# FAT42.net
KiCad netlist of a schematic drawn in Altium Designer
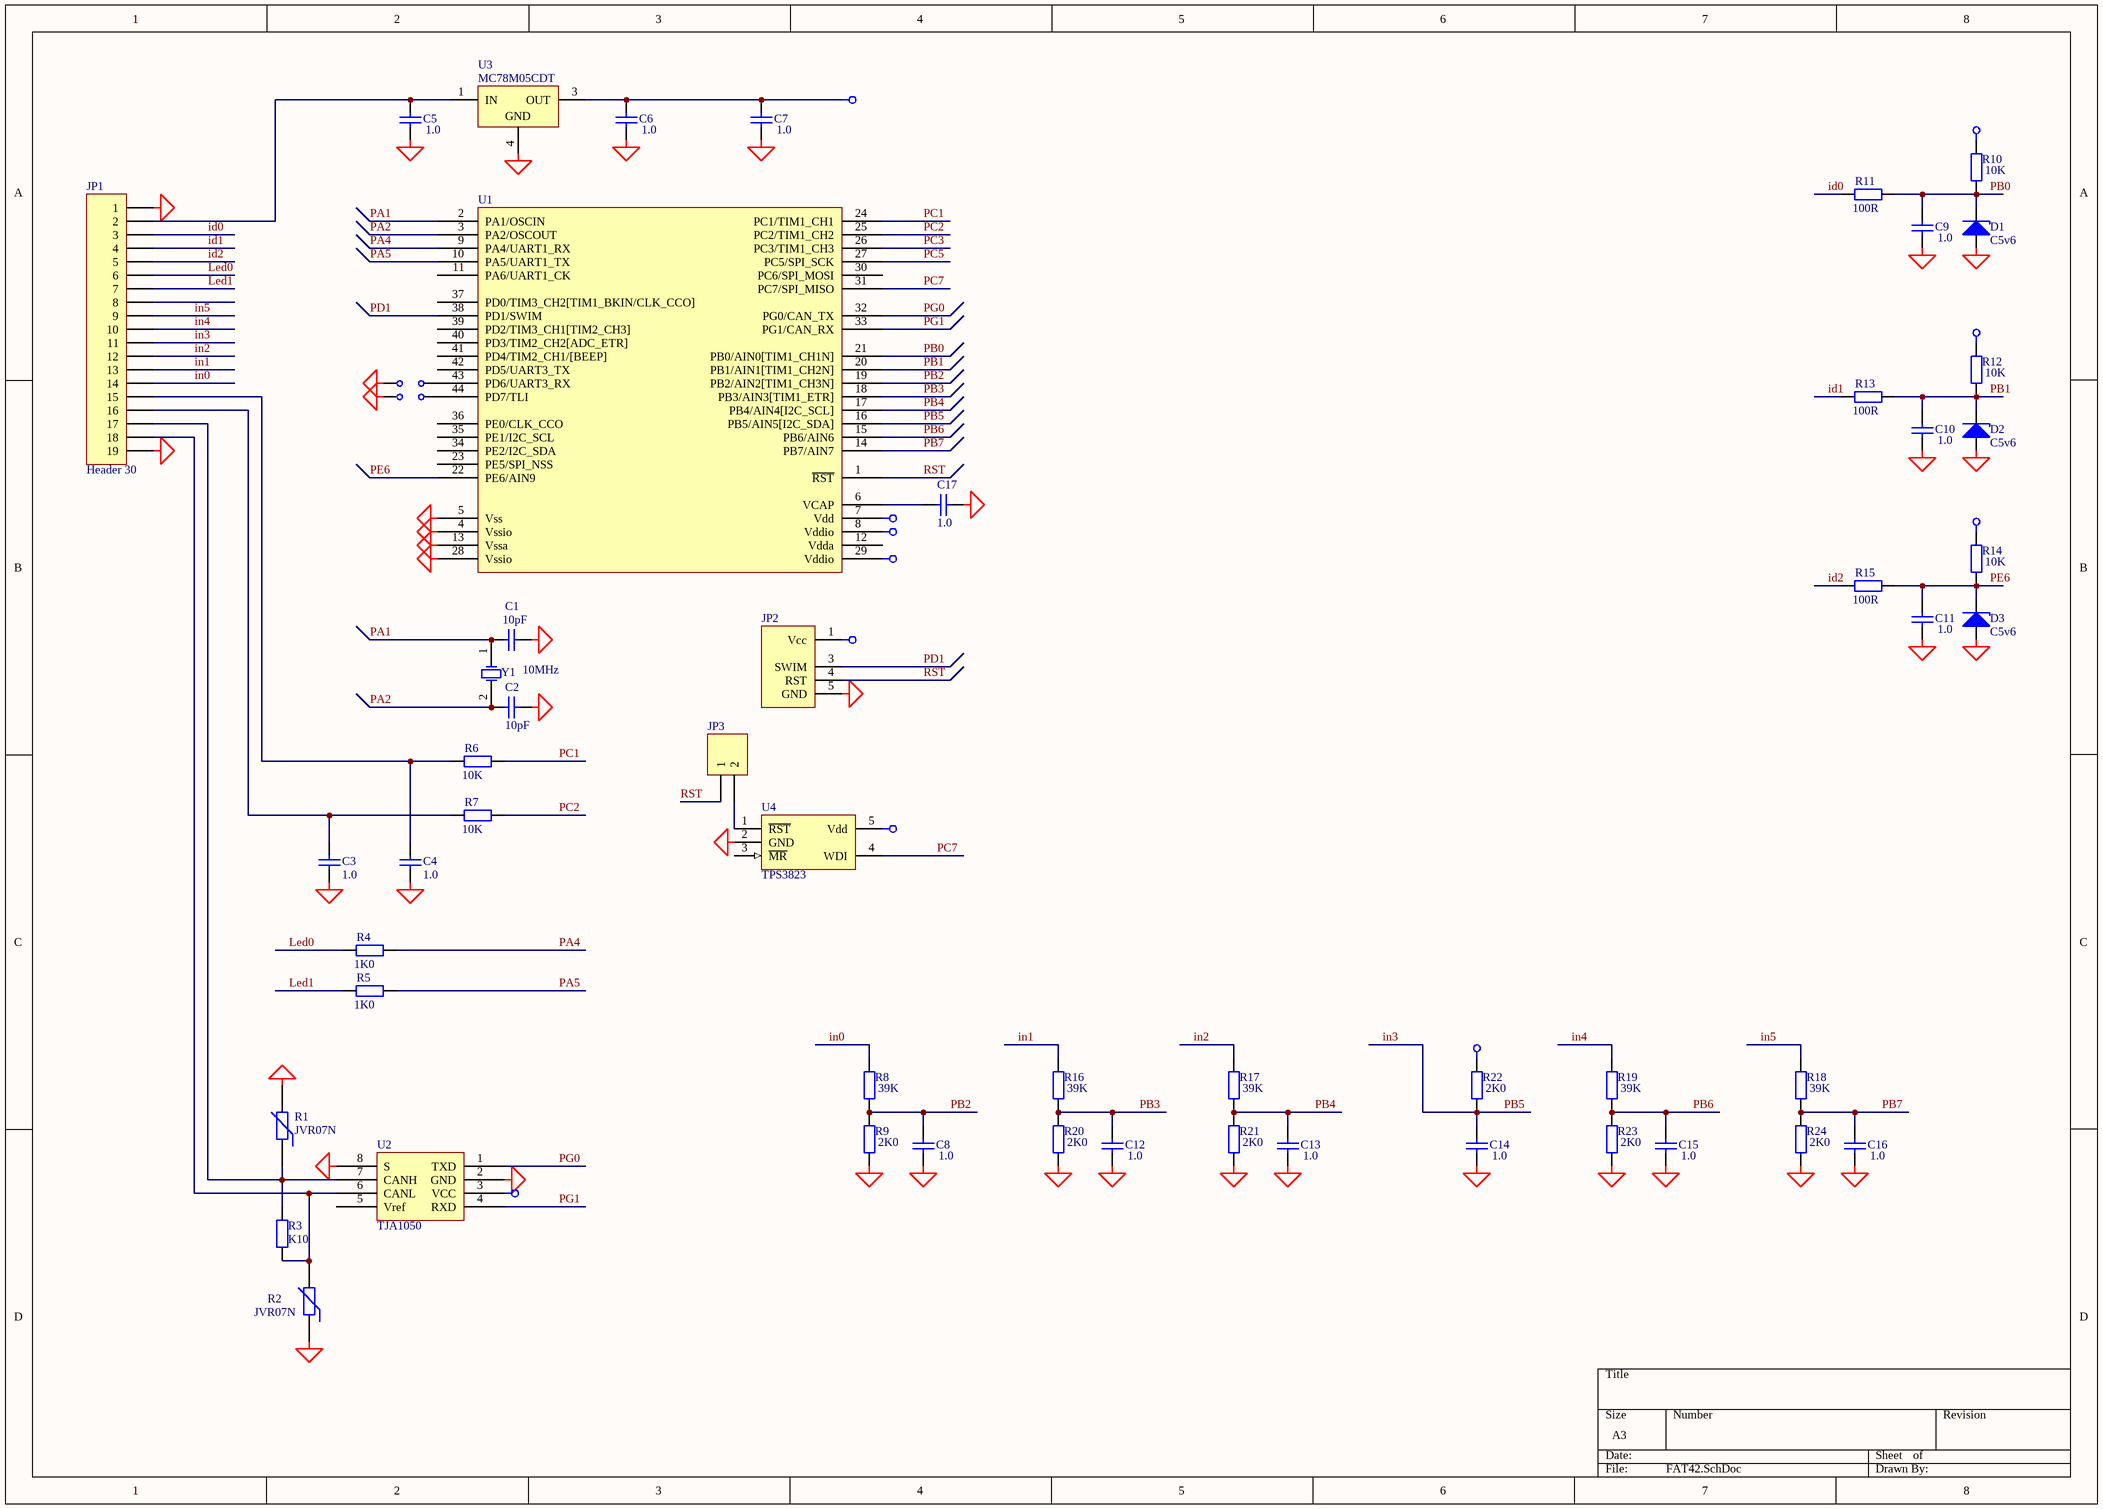
[diagram p0: FAT42.SchDoc]

(export (version "E")
  (design (tool "Eeschema 10.0.6"))
  (components
    (comp (ref "C1")
      (value "10pF")
      (footprint "_1206")
      (description "Capacitor (Semiconductor SIM Model)")
      (fields (field (name "MANUFACTURER") "Generic Components") (field (name "PUBLISHER") "Altium Limited"))
      (libsource (lib "Miscellaneous Devices") (part "Cap Semi"))
    )
    (comp (ref "C2")
      (value "10pF")
      (footprint "_1206")
      (description "Capacitor (Semiconductor SIM Model)")
      (fields (field (name "MANUFACTURER") "Generic Components") (field (name "PUBLISHER") "Altium Limited"))
      (libsource (lib "Miscellaneous Devices") (part "Cap Semi"))
    )
    (comp (ref "C3")
      (value "1.0")
      (footprint "_1206")
      (description "Capacitor (Semiconductor SIM Model)")
      (fields (field (name "MANUFACTURER") "Generic Components") (field (name "PUBLISHER") "Altium Limited"))
      (libsource (lib "Miscellaneous Devices") (part "Cap Semi"))
    )
    (comp (ref "C4")
      (value "1.0")
      (footprint "_1206")
      (description "Capacitor (Semiconductor SIM Model)")
      (fields (field (name "MANUFACTURER") "Generic Components") (field (name "PUBLISHER") "Altium Limited"))
      (libsource (lib "Miscellaneous Devices") (part "Cap Semi"))
    )
    (comp (ref "C5")
      (value "1.0")
      (footprint "_1206")
      (description "Capacitor (Semiconductor SIM Model)")
      (fields (field (name "MANUFACTURER") "Generic Components") (field (name "PUBLISHER") "Altium Limited"))
      (libsource (lib "Miscellaneous Devices") (part "Cap Semi"))
    )
    (comp (ref "C6")
      (value "1.0")
      (footprint "_1206")
      (description "Capacitor (Semiconductor SIM Model)")
      (fields (field (name "MANUFACTURER") "Generic Components") (field (name "PUBLISHER") "Altium Limited"))
      (libsource (lib "Miscellaneous Devices") (part "Cap Semi"))
    )
    (comp (ref "C7")
      (value "1.0")
      (footprint "_1206")
      (description "Capacitor (Semiconductor SIM Model)")
      (fields (field (name "MANUFACTURER") "Generic Components") (field (name "PUBLISHER") "Altium Limited"))
      (libsource (lib "Miscellaneous Devices") (part "Cap Semi"))
    )
    (comp (ref "C8")
      (value "1.0")
      (footprint "_1206")
      (description "Capacitor (Semiconductor SIM Model)")
      (fields (field (name "MANUFACTURER") "Generic Components") (field (name "PUBLISHER") "Altium Limited"))
      (libsource (lib "Miscellaneous Devices") (part "Cap Semi"))
    )
    (comp (ref "C9")
      (value "1.0")
      (footprint "_1206")
      (description "Capacitor (Semiconductor SIM Model)")
      (fields (field (name "MANUFACTURER") "Generic Components") (field (name "PUBLISHER") "Altium Limited"))
      (libsource (lib "Miscellaneous Devices") (part "Cap Semi"))
    )
    (comp (ref "C10")
      (value "1.0")
      (footprint "_1206")
      (description "Capacitor (Semiconductor SIM Model)")
      (fields (field (name "MANUFACTURER") "Generic Components") (field (name "PUBLISHER") "Altium Limited"))
      (libsource (lib "Miscellaneous Devices") (part "Cap Semi"))
    )
    (comp (ref "C11")
      (value "1.0")
      (footprint "_1206")
      (description "Capacitor (Semiconductor SIM Model)")
      (fields (field (name "MANUFACTURER") "Generic Components") (field (name "PUBLISHER") "Altium Limited"))
      (libsource (lib "Miscellaneous Devices") (part "Cap Semi"))
    )
    (comp (ref "C12")
      (value "1.0")
      (footprint "_1206")
      (description "Capacitor (Semiconductor SIM Model)")
      (fields (field (name "MANUFACTURER") "Generic Components") (field (name "PUBLISHER") "Altium Limited"))
      (libsource (lib "Miscellaneous Devices") (part "Cap Semi"))
    )
    (comp (ref "C13")
      (value "1.0")
      (footprint "_1206")
      (description "Capacitor (Semiconductor SIM Model)")
      (fields (field (name "MANUFACTURER") "Generic Components") (field (name "PUBLISHER") "Altium Limited"))
      (libsource (lib "Miscellaneous Devices") (part "Cap Semi"))
    )
    (comp (ref "C14")
      (value "1.0")
      (footprint "_1206")
      (description "Capacitor (Semiconductor SIM Model)")
      (fields (field (name "MANUFACTURER") "Generic Components") (field (name "PUBLISHER") "Altium Limited"))
      (libsource (lib "Miscellaneous Devices") (part "Cap Semi"))
    )
    (comp (ref "C15")
      (value "1.0")
      (footprint "_1206")
      (description "Capacitor (Semiconductor SIM Model)")
      (fields (field (name "MANUFACTURER") "Generic Components") (field (name "PUBLISHER") "Altium Limited"))
      (libsource (lib "Miscellaneous Devices") (part "Cap Semi"))
    )
    (comp (ref "C16")
      (value "1.0")
      (footprint "_1206")
      (description "Capacitor (Semiconductor SIM Model)")
      (fields (field (name "MANUFACTURER") "Generic Components") (field (name "PUBLISHER") "Altium Limited"))
      (libsource (lib "Miscellaneous Devices") (part "Cap Semi"))
    )
    (comp (ref "C17")
      (value "1.0")
      (footprint "_1206")
      (description "Capacitor (Semiconductor SIM Model)")
      (fields (field (name "MANUFACTURER") "Generic Components") (field (name "PUBLISHER") "Altium Limited"))
      (libsource (lib "Miscellaneous Devices") (part "Cap Semi"))
    )
    (comp (ref "D1")
      (value "C5v6")
      (footprint "_1206d")
      (description "Default Diode")
      (fields (field (name "MANUFACTURER") "Generic Components") (field (name "PUBLISHER") "Altium Limited"))
      (libsource (lib "PAL") (part "Zener"))
    )
    (comp (ref "D2")
      (value "C5v6")
      (footprint "_1206d")
      (description "Default Diode")
      (fields (field (name "MANUFACTURER") "Generic Components") (field (name "PUBLISHER") "Altium Limited"))
      (libsource (lib "PAL") (part "Zener"))
    )
    (comp (ref "D3")
      (value "C5v6")
      (footprint "_1206d")
      (description "Default Diode")
      (fields (field (name "MANUFACTURER") "Generic Components") (field (name "PUBLISHER") "Altium Limited"))
      (libsource (lib "PAL") (part "Zener"))
    )
    (comp (ref "J1")
      (value "~")
      (footprint "jmp")
      (description "Switch")
      (fields (field (name "MANUFACTURER") "Generic Components") (field (name "PUBLISHER") "Altium Limited"))
      (libsource (lib "PAL") (part "JMP"))
    )
    (comp (ref "J2")
      (value "~")
      (footprint "jmp")
      (description "Switch")
      (fields (field (name "MANUFACTURER") "Generic Components") (field (name "PUBLISHER") "Altium Limited"))
      (libsource (lib "PAL") (part "JMP"))
    )
    (comp (ref "JP1")
      (value "Header 30")
      (footprint "HDR1X19")
      (description "Header, 19-Pin")
      (fields (field (name "MANUFACTURER") "Generic Components") (field (name "PUBLISHER") "Altium Limited"))
      (libsource (lib "Miscellaneous Connectors") (part "Header 19"))
    )
    (comp (ref "JP2") (value "~") (footprint "HDR1X5_uart") (libsource (lib "PAL") (part "SWIM_CONN")))
    (comp (ref "JP3")
      (value "PLS2")
      (footprint "HDR1X2")
      (description "Header, 2-Pin")
      (fields (field (name "MANUFACTURER") "Generic Components") (field (name "PUBLISHER") "Altium Limited"))
      (libsource (lib "Miscellaneous Connectors") (part "Header 2"))
    )
    (comp (ref "R1")
      (value "JVR07N")
      (footprint "JVR07N")
      (description "Varistor (Voltage-Sensitive Resistor)")
      (fields (field (name "MANUFACTURER") "Generic Components") (field (name "PUBLISHER") "Altium Limited"))
      (libsource (lib "Miscellaneous Devices") (part "Res Varistor"))
    )
    (comp (ref "R2")
      (value "JVR07N")
      (footprint "JVR07N")
      (description "Varistor (Voltage-Sensitive Resistor)")
      (fields (field (name "MANUFACTURER") "Generic Components") (field (name "PUBLISHER") "Altium Limited"))
      (libsource (lib "Miscellaneous Devices") (part "Res Varistor"))
    )
    (comp (ref "R3")
      (value "K10")
      (footprint "_1206")
      (description "Resistor")
      (fields (field (name "MANUFACTURER") "Generic Components") (field (name "PUBLISHER") "Altium Limited"))
      (libsource (lib "") (part "Res2_4"))
    )
    (comp (ref "R4")
      (value "1K0")
      (footprint "_1206")
      (description "Resistor")
      (fields (field (name "MANUFACTURER") "Generic Components") (field (name "PUBLISHER") "Altium Limited"))
      (libsource (lib "") (part "Res2_3"))
    )
    (comp (ref "R5")
      (value "1K0")
      (footprint "_1206")
      (description "Resistor")
      (fields (field (name "MANUFACTURER") "Generic Components") (field (name "PUBLISHER") "Altium Limited"))
      (libsource (lib "") (part "Res2_3"))
    )
    (comp (ref "R6")
      (value "10K")
      (footprint "_1206")
      (description "Resistor")
      (fields (field (name "MANUFACTURER") "Generic Components") (field (name "PUBLISHER") "Altium Limited"))
      (libsource (lib "") (part "Res2_1"))
    )
    (comp (ref "R7")
      (value "10K")
      (footprint "_1206")
      (description "Resistor")
      (fields (field (name "MANUFACTURER") "Generic Components") (field (name "PUBLISHER") "Altium Limited"))
      (libsource (lib "") (part "Res2_1"))
    )
    (comp (ref "R8")
      (value "39K")
      (footprint "_1206")
      (description "Resistor")
      (fields (field (name "MANUFACTURER") "Generic Components") (field (name "PUBLISHER") "Altium Limited"))
      (libsource (lib "Miscellaneous Devices") (part "Res2"))
    )
    (comp (ref "R9")
      (value "2K0")
      (footprint "_1206")
      (description "Resistor")
      (fields (field (name "MANUFACTURER") "Generic Components") (field (name "PUBLISHER") "Altium Limited"))
      (libsource (lib "Miscellaneous Devices") (part "Res2"))
    )
    (comp (ref "R10")
      (value "10K")
      (footprint "_1206")
      (description "Resistor")
      (fields (field (name "MANUFACTURER") "Generic Components") (field (name "PUBLISHER") "Altium Limited"))
      (libsource (lib "") (part "Res2_2"))
    )
    (comp (ref "R11")
      (value "100R")
      (footprint "_1206")
      (description "Resistor")
      (fields (field (name "MANUFACTURER") "Generic Components") (field (name "PUBLISHER") "Altium Limited"))
      (libsource (lib "") (part "Res2_1"))
    )
    (comp (ref "R12")
      (value "10K")
      (footprint "_1206")
      (description "Resistor")
      (fields (field (name "MANUFACTURER") "Generic Components") (field (name "PUBLISHER") "Altium Limited"))
      (libsource (lib "") (part "Res2_2"))
    )
    (comp (ref "R13")
      (value "100R")
      (footprint "_1206")
      (description "Resistor")
      (fields (field (name "MANUFACTURER") "Generic Components") (field (name "PUBLISHER") "Altium Limited"))
      (libsource (lib "") (part "Res2_1"))
    )
    (comp (ref "R14")
      (value "10K")
      (footprint "_1206")
      (description "Resistor")
      (fields (field (name "MANUFACTURER") "Generic Components") (field (name "PUBLISHER") "Altium Limited"))
      (libsource (lib "") (part "Res2_2"))
    )
    (comp (ref "R15")
      (value "100R")
      (footprint "_1206")
      (description "Resistor")
      (fields (field (name "MANUFACTURER") "Generic Components") (field (name "PUBLISHER") "Altium Limited"))
      (libsource (lib "") (part "Res2_1"))
    )
    (comp (ref "R16")
      (value "39K")
      (footprint "_1206")
      (description "Resistor")
      (fields (field (name "MANUFACTURER") "Generic Components") (field (name "PUBLISHER") "Altium Limited"))
      (libsource (lib "Miscellaneous Devices") (part "Res2"))
    )
    (comp (ref "R17")
      (value "39K")
      (footprint "_1206")
      (description "Resistor")
      (fields (field (name "MANUFACTURER") "Generic Components") (field (name "PUBLISHER") "Altium Limited"))
      (libsource (lib "Miscellaneous Devices") (part "Res2"))
    )
    (comp (ref "R18")
      (value "39K")
      (footprint "_1206")
      (description "Resistor")
      (fields (field (name "MANUFACTURER") "Generic Components") (field (name "PUBLISHER") "Altium Limited"))
      (libsource (lib "Miscellaneous Devices") (part "Res2"))
    )
    (comp (ref "R19")
      (value "39K")
      (footprint "_1206")
      (description "Resistor")
      (fields (field (name "MANUFACTURER") "Generic Components") (field (name "PUBLISHER") "Altium Limited"))
      (libsource (lib "Miscellaneous Devices") (part "Res2"))
    )
    (comp (ref "R20")
      (value "2K0")
      (footprint "_1206")
      (description "Resistor")
      (fields (field (name "MANUFACTURER") "Generic Components") (field (name "PUBLISHER") "Altium Limited"))
      (libsource (lib "Miscellaneous Devices") (part "Res2"))
    )
    (comp (ref "R21")
      (value "2K0")
      (footprint "_1206")
      (description "Resistor")
      (fields (field (name "MANUFACTURER") "Generic Components") (field (name "PUBLISHER") "Altium Limited"))
      (libsource (lib "Miscellaneous Devices") (part "Res2"))
    )
    (comp (ref "R22")
      (value "2K0")
      (footprint "_1206")
      (description "Resistor")
      (fields (field (name "MANUFACTURER") "Generic Components") (field (name "PUBLISHER") "Altium Limited"))
      (libsource (lib "Miscellaneous Devices") (part "Res2"))
    )
    (comp (ref "R23")
      (value "2K0")
      (footprint "_1206")
      (description "Resistor")
      (fields (field (name "MANUFACTURER") "Generic Components") (field (name "PUBLISHER") "Altium Limited"))
      (libsource (lib "Miscellaneous Devices") (part "Res2"))
    )
    (comp (ref "R24")
      (value "2K0")
      (footprint "_1206")
      (description "Resistor")
      (fields (field (name "MANUFACTURER") "Generic Components") (field (name "PUBLISHER") "Altium Limited"))
      (libsource (lib "Miscellaneous Devices") (part "Res2"))
    )
    (comp (ref "U1") (value "~") (footprint "QFP10X10-G44/G10N") (libsource (lib "PAL") (part "STM8S208S6")))
    (comp (ref "U2") (value "TJA1050") (footprint "SO-G8/D5") (libsource (lib "PAL") (part "TJA1050")))
    (comp (ref "U3")
      (value "MC78M05CDT")
      (footprint "SIP-G3/Z11.05")
      (description "Three-Terminal Medium Current Positive Voltage Regulator")
      (fields (field (name "MANUFACTURER") "ON Semiconductor") (field (name "PUBLISHER") "Altium Limited"))
      (libsource (lib "ON Semi Power Mgt Voltage Regulator") (part "MC78M05CDT"))
    )
    (comp (ref "U4")
      (value "TPS3823")
      (footprint "SO-G5/P.95")
      (description "Reset IC")
      (fields
        (field (name "MANUFACTURER") "National Semiconductor")
        (field (name "PUBLISHER") "Altium Limited")
      )
      (libsource (lib "PAL") (part "TPS3823"))
    )
    (comp (ref "Y1")
      (value "10MHz")
      (footprint "QWARZ1")
      (description "Crystal Oscillator")
      (fields (field (name "MANUFACTURER") "Generic Components") (field (name "PUBLISHER") "Altium Limited"))
      (libsource (lib "Miscellaneous Devices") (part "XTAL"))
    )
  )
  (nets
    (net (code "1") (name "+5v") (class "Default")
      (node (ref "C6") (pin "2") (pinfunction "2_2") (pintype "passive"))
      (node (ref "C7") (pin "2") (pinfunction "2_2") (pintype "passive"))
      (node (ref "JP2") (pin "1") (pinfunction "Vcc_1") (pintype "passive"))
      (node (ref "R10") (pin "1") (pinfunction "1_1") (pintype "passive"))
      (node (ref "R12") (pin "1") (pinfunction "1_1") (pintype "passive"))
      (node (ref "R14") (pin "1") (pinfunction "1_1") (pintype "passive"))
      (node (ref "R22") (pin "2") (pinfunction "2_2") (pintype "passive"))
      (node (ref "U1") (pin "29") (pinfunction "Vddio_29") (pintype "passive"))
      (node (ref "U1") (pin "7") (pinfunction "Vdd_7") (pintype "passive"))
      (node (ref "U1") (pin "8") (pinfunction "Vddio_8") (pintype "passive"))
      (node (ref "U2") (pin "3") (pinfunction "VCC_3") (pintype "passive"))
      (node (ref "U3") (pin "3") (pinfunction "OUT_3") (pintype "power_in"))
      (node (ref "U4") (pin "5") (pinfunction "Vdd_5") (pintype "power_in"))
    )
    (net (code "2") (name "/Led0") (class "Default")
      (node (ref "JP1") (pin "6") (pinfunction "6_6") (pintype "passive"))
      (node (ref "R4") (pin "1") (pinfunction "1_1") (pintype "passive"))
    )
    (net (code "3") (name "/Led1") (class "Default")
      (node (ref "JP1") (pin "7") (pinfunction "7_7") (pintype "passive"))
      (node (ref "R5") (pin "1") (pinfunction "1_1") (pintype "passive"))
    )
    (net (code "4") (name "/PA1") (class "Default")
      (node (ref "C1") (pin "2") (pinfunction "2_2") (pintype "passive"))
      (node (ref "U1") (pin "2") (pinfunction "PA1/OSCIN_2") (pintype "passive"))
      (node (ref "Y1") (pin "1") (pinfunction "OSC1_1") (pintype "passive"))
    )
    (net (code "5") (name "/PA2") (class "Default")
      (node (ref "C2") (pin "2") (pinfunction "2_2") (pintype "passive"))
      (node (ref "U1") (pin "3") (pinfunction "PA2/OSCOUT_3") (pintype "passive"))
      (node (ref "Y1") (pin "2") (pinfunction "OSC2_2") (pintype "passive"))
    )
    (net (code "6") (name "/PA4") (class "Default")
      (node (ref "R4") (pin "2") (pinfunction "2_2") (pintype "passive"))
      (node (ref "U1") (pin "9") (pinfunction "PA4/UART1_RX_9") (pintype "passive"))
    )
    (net (code "7") (name "/PA5") (class "Default")
      (node (ref "R5") (pin "2") (pinfunction "2_2") (pintype "passive"))
      (node (ref "U1") (pin "10") (pinfunction "PA5/UART1_TX_10") (pintype "passive"))
    )
    (net (code "8") (name "/PB0") (class "Default")
      (node (ref "C9") (pin "2") (pinfunction "2_2") (pintype "passive"))
      (node (ref "D1") (pin "2") (pinfunction "K_2") (pintype "passive"))
      (node (ref "R10") (pin "2") (pinfunction "2_2") (pintype "passive"))
      (node (ref "R11") (pin "1") (pinfunction "1_1") (pintype "passive"))
      (node (ref "U1") (pin "21") (pinfunction "PB0/AIN0[TIM1_CH1N]_21") (pintype "passive"))
    )
    (net (code "9") (name "/PB1") (class "Default")
      (node (ref "C10") (pin "2") (pinfunction "2_2") (pintype "passive"))
      (node (ref "D2") (pin "2") (pinfunction "K_2") (pintype "passive"))
      (node (ref "R12") (pin "2") (pinfunction "2_2") (pintype "passive"))
      (node (ref "R13") (pin "1") (pinfunction "1_1") (pintype "passive"))
      (node (ref "U1") (pin "20") (pinfunction "PB1/AIN1[TIM1_CH2N]_20") (pintype "passive"))
    )
    (net (code "10") (name "/PB2") (class "Default")
      (node (ref "C8") (pin "2") (pinfunction "2_2") (pintype "passive"))
      (node (ref "R8") (pin "1") (pinfunction "1_1") (pintype "passive"))
      (node (ref "R9") (pin "2") (pinfunction "2_2") (pintype "passive"))
      (node (ref "U1") (pin "19") (pinfunction "PB2/AIN2[TIM1_CH3N]_19") (pintype "passive"))
    )
    (net (code "11") (name "/PB3") (class "Default")
      (node (ref "C12") (pin "2") (pinfunction "2_2") (pintype "passive"))
      (node (ref "R16") (pin "1") (pinfunction "1_1") (pintype "passive"))
      (node (ref "R20") (pin "2") (pinfunction "2_2") (pintype "passive"))
      (node (ref "U1") (pin "18") (pinfunction "PB3/AIN3[TIM1_ETR]_18") (pintype "passive"))
    )
    (net (code "12") (name "/PB4") (class "Default")
      (node (ref "C13") (pin "2") (pinfunction "2_2") (pintype "passive"))
      (node (ref "R17") (pin "1") (pinfunction "1_1") (pintype "passive"))
      (node (ref "R21") (pin "2") (pinfunction "2_2") (pintype "passive"))
      (node (ref "U1") (pin "17") (pinfunction "PB4/AIN4[I2C_SCL]_17") (pintype "passive"))
    )
    (net (code "13") (name "/PB5") (class "Default")
      (node (ref "C14") (pin "2") (pinfunction "2_2") (pintype "passive"))
      (node (ref "JP1") (pin "11") (pinfunction "11_11") (pintype "passive"))
      (node (ref "R22") (pin "1") (pinfunction "1_1") (pintype "passive"))
      (node (ref "U1") (pin "16") (pinfunction "PB5/AIN5[I2C_SDA]_16") (pintype "passive"))
    )
    (net (code "14") (name "/PB6") (class "Default")
      (node (ref "C15") (pin "2") (pinfunction "2_2") (pintype "passive"))
      (node (ref "R19") (pin "1") (pinfunction "1_1") (pintype "passive"))
      (node (ref "R23") (pin "2") (pinfunction "2_2") (pintype "passive"))
      (node (ref "U1") (pin "15") (pinfunction "PB6/AIN6_15") (pintype "passive"))
    )
    (net (code "15") (name "/PB7") (class "Default")
      (node (ref "C16") (pin "2") (pinfunction "2_2") (pintype "passive"))
      (node (ref "R18") (pin "1") (pinfunction "1_1") (pintype "passive"))
      (node (ref "R24") (pin "2") (pinfunction "2_2") (pintype "passive"))
      (node (ref "U1") (pin "14") (pinfunction "PB7/AIN7_14") (pintype "passive"))
    )
    (net (code "16") (name "/PC1") (class "Default")
      (node (ref "R6") (pin "1") (pinfunction "1_1") (pintype "passive"))
      (node (ref "U1") (pin "24") (pinfunction "PC1/TIM1_CH1_24") (pintype "passive"))
    )
    (net (code "17") (name "/PC2") (class "Default")
      (node (ref "R7") (pin "1") (pinfunction "1_1") (pintype "passive"))
      (node (ref "U1") (pin "25") (pinfunction "PC2/TIM1_CH2_25") (pintype "passive"))
    )
    (net (code "18") (name "/PC3") (class "Default")
      (node (ref "U1") (pin "26") (pinfunction "PC3/TIM1_CH3_26") (pintype "passive"))
    )
    (net (code "19") (name "/PC5") (class "Default")
      (node (ref "U1") (pin "27") (pinfunction "PC5/SPI_SCK_27") (pintype "passive"))
    )
    (net (code "20") (name "/PC7") (class "Default")
      (node (ref "U1") (pin "31") (pinfunction "PC7/SPI_MISO_31") (pintype "passive"))
      (node (ref "U4") (pin "4") (pinfunction "WDI_4") (pintype "passive"))
    )
    (net (code "21") (name "/PD1") (class "Default")
      (node (ref "JP2") (pin "3") (pinfunction "SWIM_3") (pintype "passive"))
      (node (ref "U1") (pin "38") (pinfunction "PD1/SWIM_38") (pintype "passive"))
    )
    (net (code "22") (name "/PE6") (class "Default")
      (node (ref "C11") (pin "2") (pinfunction "2_2") (pintype "passive"))
      (node (ref "D3") (pin "2") (pinfunction "K_2") (pintype "passive"))
      (node (ref "R14") (pin "2") (pinfunction "2_2") (pintype "passive"))
      (node (ref "R15") (pin "1") (pinfunction "1_1") (pintype "passive"))
      (node (ref "U1") (pin "22") (pinfunction "PE6/AIN9_22") (pintype "passive"))
    )
    (net (code "23") (name "/PG0") (class "Default")
      (node (ref "U1") (pin "32") (pinfunction "PG0/CAN_TX_32") (pintype "passive"))
      (node (ref "U2") (pin "1") (pinfunction "TXD_1") (pintype "passive"))
    )
    (net (code "24") (name "/PG1") (class "Default")
      (node (ref "U1") (pin "33") (pinfunction "PG1/CAN_RX_33") (pintype "passive"))
      (node (ref "U2") (pin "4") (pinfunction "RXD_4") (pintype "passive"))
    )
    (net (code "25") (name "/RST") (class "Default")
      (node (ref "JP2") (pin "4") (pinfunction "RST_4") (pintype "passive"))
      (node (ref "JP3") (pin "1") (pinfunction "1_1") (pintype "passive"))
      (node (ref "U1") (pin "1") (pinfunction "~{RST}_1") (pintype "passive"))
    )
    (net (code "26") (name "/id0") (class "Default")
      (node (ref "JP1") (pin "3") (pinfunction "3_3") (pintype "passive"))
      (node (ref "R11") (pin "2") (pinfunction "2_2") (pintype "passive"))
    )
    (net (code "27") (name "/id1") (class "Default")
      (node (ref "JP1") (pin "4") (pinfunction "4_4") (pintype "passive"))
      (node (ref "R13") (pin "2") (pinfunction "2_2") (pintype "passive"))
    )
    (net (code "28") (name "/id2") (class "Default")
      (node (ref "JP1") (pin "5") (pinfunction "5_5") (pintype "passive"))
      (node (ref "R15") (pin "2") (pinfunction "2_2") (pintype "passive"))
    )
    (net (code "29") (name "/in0") (class "Default")
      (node (ref "JP1") (pin "14") (pinfunction "14_14") (pintype "passive"))
      (node (ref "R8") (pin "2") (pinfunction "2_2") (pintype "passive"))
    )
    (net (code "30") (name "/in1") (class "Default")
      (node (ref "JP1") (pin "13") (pinfunction "13_13") (pintype "passive"))
      (node (ref "R16") (pin "2") (pinfunction "2_2") (pintype "passive"))
    )
    (net (code "31") (name "/in2") (class "Default")
      (node (ref "JP1") (pin "12") (pinfunction "12_12") (pintype "passive"))
      (node (ref "R17") (pin "2") (pinfunction "2_2") (pintype "passive"))
    )
    (net (code "32") (name "/in4") (class "Default")
      (node (ref "JP1") (pin "10") (pinfunction "10_10") (pintype "passive"))
      (node (ref "R19") (pin "2") (pinfunction "2_2") (pintype "passive"))
    )
    (net (code "33") (name "/in5") (class "Default")
      (node (ref "JP1") (pin "9") (pinfunction "9_9") (pintype "passive"))
      (node (ref "R18") (pin "2") (pinfunction "2_2") (pintype "passive"))
    )
    (net (code "34") (name "GND") (class "Default")
      (node (ref "C1") (pin "1") (pinfunction "1_1") (pintype "passive"))
      (node (ref "C10") (pin "1") (pinfunction "1_1") (pintype "passive"))
      (node (ref "C11") (pin "1") (pinfunction "1_1") (pintype "passive"))
      (node (ref "C12") (pin "1") (pinfunction "1_1") (pintype "passive"))
      (node (ref "C13") (pin "1") (pinfunction "1_1") (pintype "passive"))
      (node (ref "C14") (pin "1") (pinfunction "1_1") (pintype "passive"))
      (node (ref "C15") (pin "1") (pinfunction "1_1") (pintype "passive"))
      (node (ref "C16") (pin "1") (pinfunction "1_1") (pintype "passive"))
      (node (ref "C17") (pin "1") (pinfunction "1_1") (pintype "passive"))
      (node (ref "C2") (pin "1") (pinfunction "1_1") (pintype "passive"))
      (node (ref "C3") (pin "1") (pinfunction "1_1") (pintype "passive"))
      (node (ref "C4") (pin "1") (pinfunction "1_1") (pintype "passive"))
      (node (ref "C5") (pin "1") (pinfunction "1_1") (pintype "passive"))
      (node (ref "C6") (pin "1") (pinfunction "1_1") (pintype "passive"))
      (node (ref "C7") (pin "1") (pinfunction "1_1") (pintype "passive"))
      (node (ref "C8") (pin "1") (pinfunction "1_1") (pintype "passive"))
      (node (ref "C9") (pin "1") (pinfunction "1_1") (pintype "passive"))
      (node (ref "D1") (pin "1") (pinfunction "A_1") (pintype "passive"))
      (node (ref "D2") (pin "1") (pinfunction "A_1") (pintype "passive"))
      (node (ref "D3") (pin "1") (pinfunction "A_1") (pintype "passive"))
      (node (ref "J1") (pin "1") (pinfunction "1_1") (pintype "passive"))
      (node (ref "J2") (pin "1") (pinfunction "1_1") (pintype "passive"))
      (node (ref "JP1") (pin "1") (pinfunction "1_1") (pintype "passive"))
      (node (ref "JP1") (pin "19") (pinfunction "19_19") (pintype "passive"))
      (node (ref "JP2") (pin "5") (pinfunction "GND_5") (pintype "passive"))
      (node (ref "R1") (pin "2") (pinfunction "2_2") (pintype "passive"))
      (node (ref "R2") (pin "1") (pinfunction "1_1") (pintype "passive"))
      (node (ref "R20") (pin "1") (pinfunction "1_1") (pintype "passive"))
      (node (ref "R21") (pin "1") (pinfunction "1_1") (pintype "passive"))
      (node (ref "R23") (pin "1") (pinfunction "1_1") (pintype "passive"))
      (node (ref "R24") (pin "1") (pinfunction "1_1") (pintype "passive"))
      (node (ref "R9") (pin "1") (pinfunction "1_1") (pintype "passive"))
      (node (ref "U1") (pin "13") (pinfunction "Vssa_13") (pintype "passive"))
      (node (ref "U1") (pin "28") (pinfunction "Vssio_28") (pintype "passive"))
      (node (ref "U1") (pin "4") (pinfunction "Vssio_4") (pintype "passive"))
      (node (ref "U1") (pin "5") (pinfunction "Vss_5") (pintype "passive"))
      (node (ref "U2") (pin "2") (pinfunction "GND_2") (pintype "passive"))
      (node (ref "U2") (pin "8") (pinfunction "S_8") (pintype "passive"))
      (node (ref "U3") (pin "4") (pinfunction "GND_4") (pintype "power_in"))
      (node (ref "U4") (pin "2") (pinfunction "GND_2") (pintype "power_in"))
    )
    (net (code "35") (name "Net-(C3-Pad2)") (class "Default")
      (node (ref "C3") (pin "2") (pinfunction "2_2") (pintype "passive"))
      (node (ref "JP1") (pin "16") (pinfunction "16_16") (pintype "passive"))
      (node (ref "R7") (pin "2") (pinfunction "2_2") (pintype "passive"))
    )
    (net (code "36") (name "Net-(C4-Pad2)") (class "Default")
      (node (ref "C4") (pin "2") (pinfunction "2_2") (pintype "passive"))
      (node (ref "JP1") (pin "15") (pinfunction "15_15") (pintype "passive"))
      (node (ref "R6") (pin "2") (pinfunction "2_2") (pintype "passive"))
    )
    (net (code "37") (name "Net-(U1-PD6{slash}UART3_RX)") (class "Default")
      (node (ref "J1") (pin "2") (pinfunction "2_2") (pintype "passive"))
      (node (ref "U1") (pin "43") (pinfunction "PD6/UART3_RX_43") (pintype "passive"))
    )
    (net (code "38") (name "Net-(U1-PD7{slash}TLI)") (class "Default")
      (node (ref "J2") (pin "2") (pinfunction "2_2") (pintype "passive"))
      (node (ref "U1") (pin "44") (pinfunction "PD7/TLI_44") (pintype "passive"))
    )
    (net (code "39") (name "Net-(U1-VCAP)") (class "Default")
      (node (ref "C17") (pin "2") (pinfunction "2_2") (pintype "passive"))
      (node (ref "U1") (pin "6") (pinfunction "VCAP_6") (pintype "passive"))
    )
    (net (code "40") (name "Net-(U2-CANH)") (class "Default")
      (node (ref "JP1") (pin "17") (pinfunction "17_17") (pintype "passive"))
      (node (ref "R1") (pin "1") (pinfunction "1_1") (pintype "passive"))
      (node (ref "R3") (pin "2") (pinfunction "2_2") (pintype "passive"))
      (node (ref "U2") (pin "7") (pinfunction "CANH_7") (pintype "passive"))
    )
    (net (code "41") (name "Net-(U2-CANL)") (class "Default")
      (node (ref "JP1") (pin "18") (pinfunction "18_18") (pintype "passive"))
      (node (ref "R2") (pin "2") (pinfunction "2_2") (pintype "passive"))
      (node (ref "R3") (pin "1") (pinfunction "1_1") (pintype "passive"))
      (node (ref "U2") (pin "6") (pinfunction "CANL_6") (pintype "passive"))
    )
    (net (code "42") (name "Net-(U3-IN)") (class "Default")
      (node (ref "C5") (pin "2") (pinfunction "2_2") (pintype "passive"))
      (node (ref "JP1") (pin "2") (pinfunction "2_2") (pintype "passive"))
      (node (ref "U3") (pin "1") (pinfunction "IN_1") (pintype "power_in"))
    )
    (net (code "43") (name "Net-(U4-~{RST})") (class "Default")
      (node (ref "JP3") (pin "2") (pinfunction "2_2") (pintype "passive"))
      (node (ref "U4") (pin "1") (pinfunction "~{RST}_1") (pintype "power_in"))
    )
    (net (code "44") (name "unconnected-(JP1-Pad8)") (class "Default")
      (node (ref "JP1") (pin "8") (pinfunction "8_8") (pintype "passive"))
    )
    (net (code "45") (name "unconnected-(U1-PA6{slash}UART1_CK-Pad11)") (class "Default")
      (node (ref "U1") (pin "11") (pinfunction "PA6/UART1_CK_11") (pintype "passive"))
    )
    (net (code "46") (name "unconnected-(U1-PC6{slash}SPI_MOSI-Pad30)") (class "Default")
      (node (ref "U1") (pin "30") (pinfunction "PC6/SPI_MOSI_30") (pintype "passive"))
    )
    (net (code "47") (name "unconnected-(U1-PD0{slash}TIM3_CH2[TIM1_BKIN{slash}CLK_CCO]-Pad37)") (class "Default")
      (node (ref "U1") (pin "37") (pinfunction "PD0/TIM3_CH2[TIM1_BKIN/CLK_CCO]_37") (pintype "passive"))
    )
    (net (code "48") (name "unconnected-(U1-PD2{slash}TIM3_CH1[TIM2_CH3]-Pad39)") (class "Default")
      (node (ref "U1") (pin "39") (pinfunction "PD2/TIM3_CH1[TIM2_CH3]_39") (pintype "passive"))
    )
    (net (code "49") (name "unconnected-(U1-PD3{slash}TIM2_CH2[ADC_ETR]-Pad40)") (class "Default")
      (node (ref "U1") (pin "40") (pinfunction "PD3/TIM2_CH2[ADC_ETR]_40") (pintype "passive"))
    )
    (net (code "50") (name "unconnected-(U1-PD4{slash}TIM2_CH1{slash}[BEEP]-Pad41)") (class "Default")
      (node (ref "U1") (pin "41") (pinfunction "PD4/TIM2_CH1/[BEEP]_41") (pintype "passive"))
    )
    (net (code "51") (name "unconnected-(U1-PD5{slash}UART3_TX-Pad42)") (class "Default")
      (node (ref "U1") (pin "42") (pinfunction "PD5/UART3_TX_42") (pintype "passive"))
    )
    (net (code "52") (name "unconnected-(U1-PE0{slash}CLK_CCO-Pad36)") (class "Default")
      (node (ref "U1") (pin "36") (pinfunction "PE0/CLK_CCO_36") (pintype "passive"))
    )
    (net (code "53") (name "unconnected-(U1-PE1{slash}I2C_SCL-Pad35)") (class "Default")
      (node (ref "U1") (pin "35") (pinfunction "PE1/I2C_SCL_35") (pintype "passive"))
    )
    (net (code "54") (name "unconnected-(U1-PE2{slash}I2C_SDA-Pad34)") (class "Default")
      (node (ref "U1") (pin "34") (pinfunction "PE2/I2C_SDA_34") (pintype "passive"))
    )
    (net (code "55") (name "unconnected-(U1-PE5{slash}SPI_NSS-Pad23)") (class "Default")
      (node (ref "U1") (pin "23") (pinfunction "PE5/SPI_NSS_23") (pintype "passive"))
    )
    (net (code "56") (name "unconnected-(U1-Vdda-Pad12)") (class "Default")
      (node (ref "U1") (pin "12") (pinfunction "Vdda_12") (pintype "passive"))
    )
    (net (code "57") (name "unconnected-(U2-Vref-Pad5)") (class "Default")
      (node (ref "U2") (pin "5") (pinfunction "Vref_5") (pintype "passive"))
    )
    (net (code "58") (name "unconnected-(U4-~{MR}-Pad3)") (class "Default")
      (node (ref "U4") (pin "3") (pinfunction "~{MR}_3") (pintype "input"))
    )
  )
)
